# V2.net
KiCad netlist of a schematic drawn in EAGLE
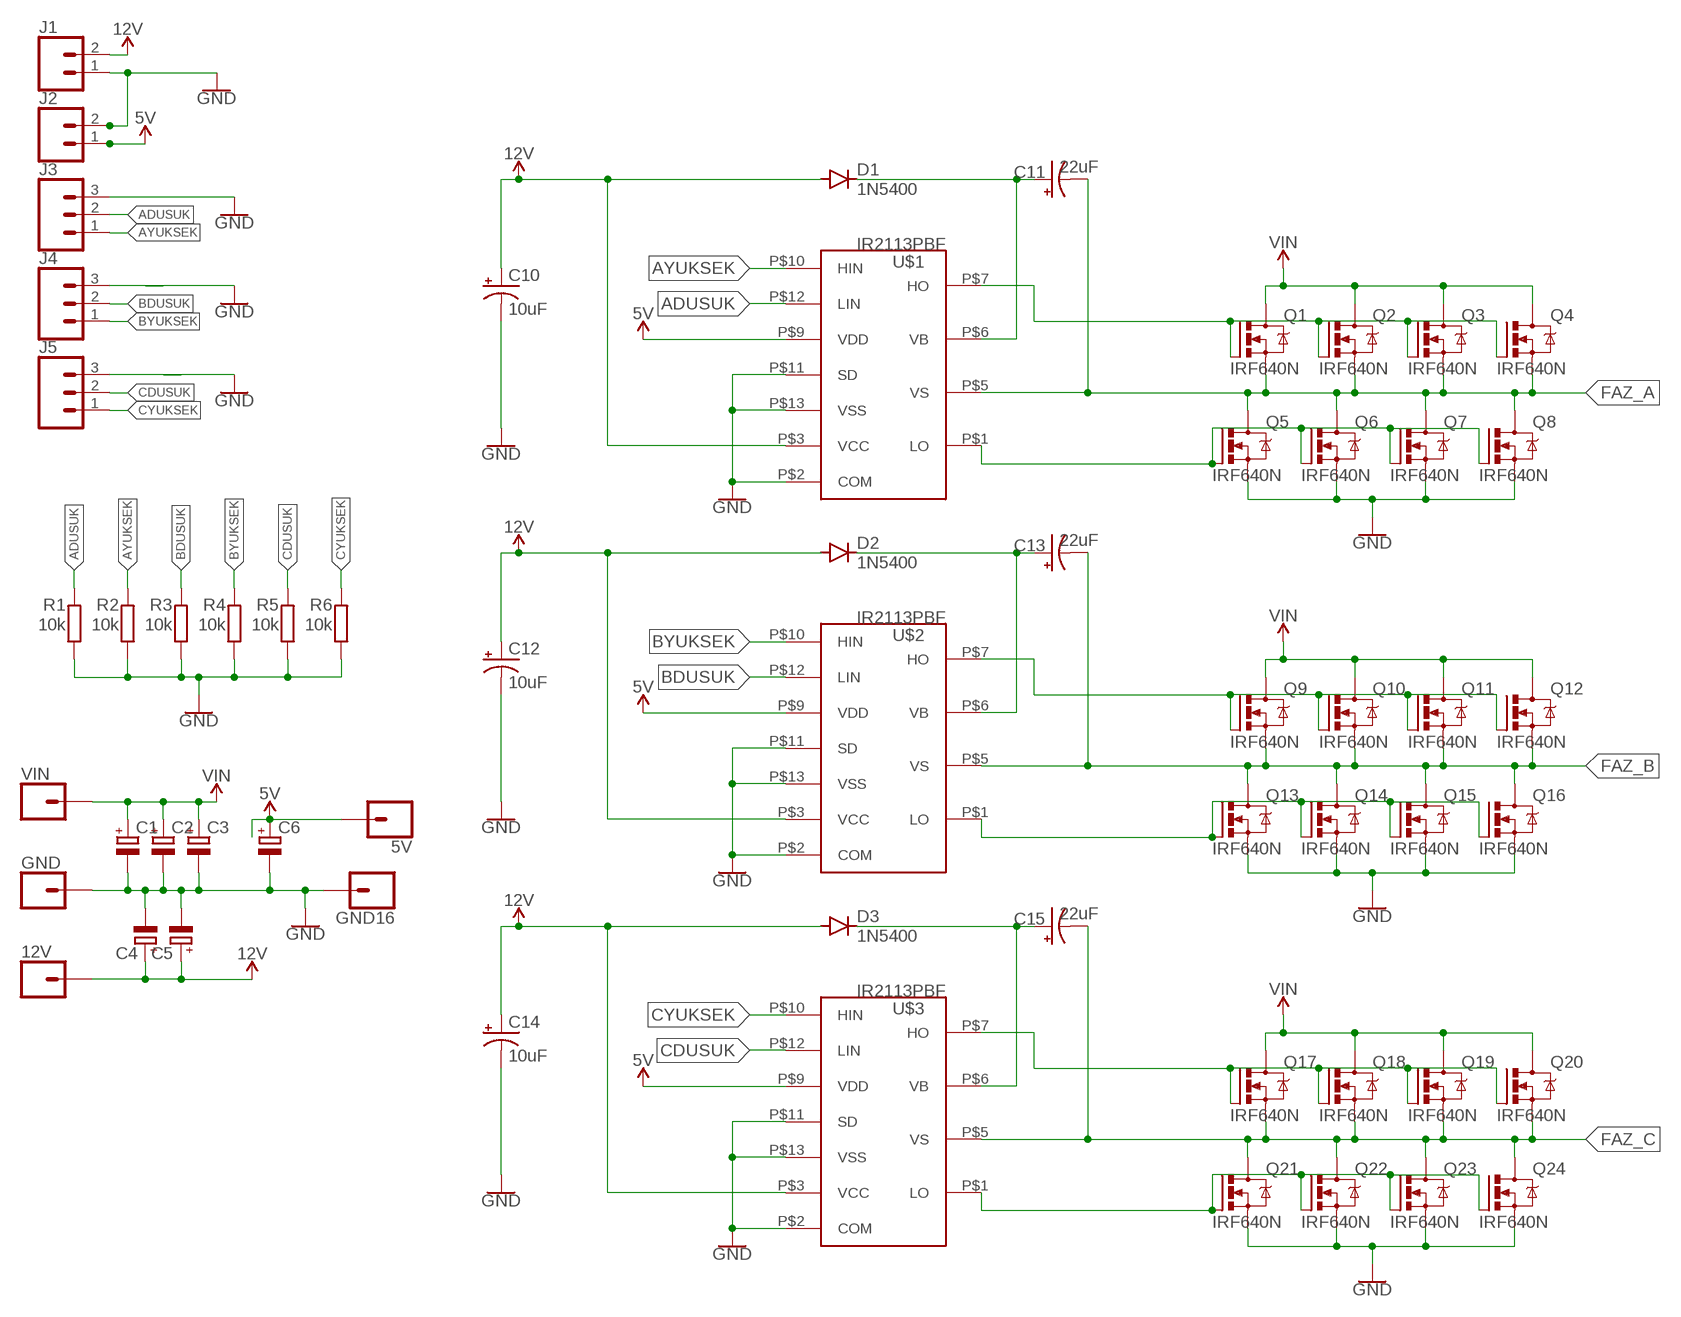
[diagram p0: schematic, sheet 1]

(export (version "E")
  (design (tool "Eeschema 10.0.6"))
  (components
    (comp (ref "5V")
      (value "CONN_01SNAP-MALE")
      (footprint "eagle-import:SNAP-MALE")
      (libsource (lib "eagle-import") (part "CONN_01SNAP-MALE"))
    )
    (comp (ref "12V")
      (value "CONN_01SNAP-MALE")
      (footprint "eagle-import:SNAP-MALE")
      (libsource (lib "eagle-import") (part "CONN_01SNAP-MALE"))
    )
    (comp (ref "C1")
      (value "16MM-DIA-CAPASITOR")
      (footprint "eagle-import:16MM-DIA-CAPASITOR")
      (libsource (lib "eagle-import") (part "16MM-DIA-CAPASITOR"))
    )
    (comp (ref "C2")
      (value "16MM-DIA-CAPASITOR")
      (footprint "eagle-import:16MM-DIA-CAPASITOR")
      (libsource (lib "eagle-import") (part "16MM-DIA-CAPASITOR"))
    )
    (comp (ref "C3")
      (value "16MM-DIA-CAPASITOR")
      (footprint "eagle-import:16MM-DIA-CAPASITOR")
      (libsource (lib "eagle-import") (part "16MM-DIA-CAPASITOR"))
    )
    (comp (ref "C4")
      (value "16MM-DIA-CAPASITOR")
      (footprint "eagle-import:16MM-DIA-CAPASITOR")
      (libsource (lib "eagle-import") (part "16MM-DIA-CAPASITOR"))
    )
    (comp (ref "C5")
      (value "16MM-DIA-CAPASITOR")
      (footprint "eagle-import:16MM-DIA-CAPASITOR")
      (libsource (lib "eagle-import") (part "16MM-DIA-CAPASITOR"))
    )
    (comp (ref "C6")
      (value "C-POL_RADIAL-25MM-DIA")
      (footprint "eagle-import:CAPPRD550W110D1250H2500B")
      (libsource (lib "eagle-import") (part "C-POLRADIAL-25MM-DIA_"))
    )
    (comp (ref "C10")
      (value "10uF")
      (footprint "eagle-import:CPOL-RADIAL-2.5MM-5MM")
      (libsource (lib "eagle-import") (part "10UF-POLAR-RADIAL-2.5MM-25V-20%"))
    )
    (comp (ref "C11")
      (value "22uF")
      (footprint "eagle-import:CPOL-RADIAL-2.5MM-5MM")
      (libsource (lib "eagle-import") (part "10UF-POLAR-RADIAL-2.5MM-25V-20%"))
    )
    (comp (ref "C12")
      (value "10uF")
      (footprint "eagle-import:CPOL-RADIAL-2.5MM-5MM")
      (libsource (lib "eagle-import") (part "10UF-POLAR-RADIAL-2.5MM-25V-20%"))
    )
    (comp (ref "C13")
      (value "22uF")
      (footprint "eagle-import:CPOL-RADIAL-2.5MM-5MM")
      (libsource (lib "eagle-import") (part "10UF-POLAR-RADIAL-2.5MM-25V-20%"))
    )
    (comp (ref "C14")
      (value "10uF")
      (footprint "eagle-import:CPOL-RADIAL-2.5MM-5MM")
      (libsource (lib "eagle-import") (part "10UF-POLAR-RADIAL-2.5MM-25V-20%"))
    )
    (comp (ref "C15")
      (value "22uF")
      (footprint "eagle-import:CPOL-RADIAL-2.5MM-5MM")
      (libsource (lib "eagle-import") (part "10UF-POLAR-RADIAL-2.5MM-25V-20%"))
    )
    (comp (ref "D1")
      (value "1N5400")
      (footprint "eagle-import:DO201-15")
      (libsource (lib "eagle-import") (part "1N5400"))
    )
    (comp (ref "D2")
      (value "1N5400")
      (footprint "eagle-import:DO201-15")
      (libsource (lib "eagle-import") (part "1N5400"))
    )
    (comp (ref "D3")
      (value "1N5400")
      (footprint "eagle-import:DO201-15")
      (libsource (lib "eagle-import") (part "1N5400"))
    )
    (comp (ref "GND")
      (value "CONN_01SNAP-MALE")
      (footprint "eagle-import:SNAP-MALE")
      (libsource (lib "eagle-import") (part "CONN_01SNAP-MALE"))
    )
    (comp (ref "GND16")
      (value "CONN_01SNAP-MALE")
      (footprint "eagle-import:SNAP-MALE")
      (libsource (lib "eagle-import") (part "CONN_01SNAP-MALE"))
    )
    (comp (ref "J1")
      (value "CONN_025MM")
      (footprint "eagle-import:SCREWTERMINAL-5MM-2")
      (libsource (lib "eagle-import") (part "CONN_025MM"))
    )
    (comp (ref "J2")
      (value "CONN_025MM")
      (footprint "eagle-import:SCREWTERMINAL-5MM-2")
      (libsource (lib "eagle-import") (part "CONN_025MM"))
    )
    (comp (ref "J3")
      (value "CONN_03-SCREW-5MM")
      (footprint "eagle-import:SCREWTERMINAL-5MM-3")
      (libsource (lib "eagle-import") (part "CONN_03-SCREW-5MM"))
    )
    (comp (ref "J4")
      (value "CONN_03-SCREW-5MM")
      (footprint "eagle-import:SCREWTERMINAL-5MM-3")
      (libsource (lib "eagle-import") (part "CONN_03-SCREW-5MM"))
    )
    (comp (ref "J5")
      (value "CONN_03-SCREW-5MM")
      (footprint "eagle-import:SCREWTERMINAL-5MM-3")
      (libsource (lib "eagle-import") (part "CONN_03-SCREW-5MM"))
    )
    (comp (ref "Q1")
      (value "IRF640N")
      (footprint "eagle-import:TO-220-PAD")
      (libsource (lib "eagle-import") (part "IRF640N"))
    )
    (comp (ref "Q2")
      (value "IRF640N")
      (footprint "eagle-import:TO-220-PAD")
      (libsource (lib "eagle-import") (part "IRF640N"))
    )
    (comp (ref "Q3")
      (value "IRF640N")
      (footprint "eagle-import:TO-220-PAD")
      (libsource (lib "eagle-import") (part "IRF640N"))
    )
    (comp (ref "Q4")
      (value "IRF640N")
      (footprint "eagle-import:TO-220-PAD")
      (libsource (lib "eagle-import") (part "IRF640N"))
    )
    (comp (ref "Q5")
      (value "IRF640N")
      (footprint "eagle-import:TO-220-PAD")
      (libsource (lib "eagle-import") (part "IRF640N"))
    )
    (comp (ref "Q6")
      (value "IRF640N")
      (footprint "eagle-import:TO-220-PAD")
      (libsource (lib "eagle-import") (part "IRF640N"))
    )
    (comp (ref "Q7")
      (value "IRF640N")
      (footprint "eagle-import:TO-220-PAD")
      (libsource (lib "eagle-import") (part "IRF640N"))
    )
    (comp (ref "Q8")
      (value "IRF640N")
      (footprint "eagle-import:TO-220-PAD")
      (libsource (lib "eagle-import") (part "IRF640N"))
    )
    (comp (ref "Q9")
      (value "IRF640N")
      (footprint "eagle-import:TO-220-PAD")
      (libsource (lib "eagle-import") (part "IRF640N"))
    )
    (comp (ref "Q10")
      (value "IRF640N")
      (footprint "eagle-import:TO-220-PAD")
      (libsource (lib "eagle-import") (part "IRF640N"))
    )
    (comp (ref "Q11")
      (value "IRF640N")
      (footprint "eagle-import:TO-220-PAD")
      (libsource (lib "eagle-import") (part "IRF640N"))
    )
    (comp (ref "Q12")
      (value "IRF640N")
      (footprint "eagle-import:TO-220-PAD")
      (libsource (lib "eagle-import") (part "IRF640N"))
    )
    (comp (ref "Q13")
      (value "IRF640N")
      (footprint "eagle-import:TO-220-PAD")
      (libsource (lib "eagle-import") (part "IRF640N"))
    )
    (comp (ref "Q14")
      (value "IRF640N")
      (footprint "eagle-import:TO-220-PAD")
      (libsource (lib "eagle-import") (part "IRF640N"))
    )
    (comp (ref "Q15")
      (value "IRF640N")
      (footprint "eagle-import:TO-220-PAD")
      (libsource (lib "eagle-import") (part "IRF640N"))
    )
    (comp (ref "Q16")
      (value "IRF640N")
      (footprint "eagle-import:TO-220-PAD")
      (libsource (lib "eagle-import") (part "IRF640N"))
    )
    (comp (ref "Q17")
      (value "IRF640N")
      (footprint "eagle-import:TO-220-PAD")
      (libsource (lib "eagle-import") (part "IRF640N"))
    )
    (comp (ref "Q18")
      (value "IRF640N")
      (footprint "eagle-import:TO-220-PAD")
      (libsource (lib "eagle-import") (part "IRF640N"))
    )
    (comp (ref "Q19")
      (value "IRF640N")
      (footprint "eagle-import:TO-220-PAD")
      (libsource (lib "eagle-import") (part "IRF640N"))
    )
    (comp (ref "Q20")
      (value "IRF640N")
      (footprint "eagle-import:TO-220-PAD")
      (libsource (lib "eagle-import") (part "IRF640N"))
    )
    (comp (ref "Q21")
      (value "IRF640N")
      (footprint "eagle-import:TO-220-PAD")
      (libsource (lib "eagle-import") (part "IRF640N"))
    )
    (comp (ref "Q22")
      (value "IRF640N")
      (footprint "eagle-import:TO-220-PAD")
      (libsource (lib "eagle-import") (part "IRF640N"))
    )
    (comp (ref "Q23")
      (value "IRF640N")
      (footprint "eagle-import:TO-220-PAD")
      (libsource (lib "eagle-import") (part "IRF640N"))
    )
    (comp (ref "Q24")
      (value "IRF640N")
      (footprint "eagle-import:TO-220-PAD")
      (libsource (lib "eagle-import") (part "IRF640N"))
    )
    (comp (ref "R1")
      (value "10k")
      (footprint "eagle-import:0207_10")
      (libsource (lib "eagle-import") (part "R-EU_0207/10"))
    )
    (comp (ref "R2")
      (value "10k")
      (footprint "eagle-import:0207_10")
      (libsource (lib "eagle-import") (part "R-EU_0207/10"))
    )
    (comp (ref "R3")
      (value "10k")
      (footprint "eagle-import:0207_10")
      (libsource (lib "eagle-import") (part "R-EU_0207/10"))
    )
    (comp (ref "R4")
      (value "10k")
      (footprint "eagle-import:0207_10")
      (libsource (lib "eagle-import") (part "R-EU_0207/10"))
    )
    (comp (ref "R5")
      (value "10k")
      (footprint "eagle-import:0207_10")
      (libsource (lib "eagle-import") (part "R-EU_0207/10"))
    )
    (comp (ref "R6")
      (value "10k")
      (footprint "eagle-import:0207_10")
      (libsource (lib "eagle-import") (part "R-EU_0207/10"))
    )
    (comp (ref "U$1")
      (value "IR2113PBF")
      (footprint "eagle-import:PDIP-14")
      (libsource (lib "eagle-import") (part "IR2113PBF"))
    )
    (comp (ref "U$2")
      (value "IR2113PBF")
      (footprint "eagle-import:PDIP-14")
      (libsource (lib "eagle-import") (part "IR2113PBF"))
    )
    (comp (ref "U$3")
      (value "IR2113PBF")
      (footprint "eagle-import:PDIP-14")
      (libsource (lib "eagle-import") (part "IR2113PBF"))
    )
    (comp (ref "VIN")
      (value "CONN_01SNAP-MALE")
      (footprint "eagle-import:SNAP-MALE")
      (libsource (lib "eagle-import") (part "CONN_01SNAP-MALE"))
    )
  )
  (nets
    (net (code "1") (name "5V") (class "Default")
      (node (ref "5V") (pin "2") (pinfunction "1_2") (pintype "passive"))
      (node (ref "C6") (pin "1") (pinfunction "+_1") (pintype "passive"))
      (node (ref "J2") (pin "1") (pinfunction "1_1") (pintype "passive"))
      (node (ref "U$1") (pin "P$9") (pinfunction "VDD_P$9") (pintype "bidirectional"))
      (node (ref "U$2") (pin "P$9") (pinfunction "VDD_P$9") (pintype "bidirectional"))
      (node (ref "U$3") (pin "P$9") (pinfunction "VDD_P$9") (pintype "bidirectional"))
    )
    (net (code "2") (name "12V") (class "Default")
      (node (ref "12V") (pin "2") (pinfunction "1_2") (pintype "passive"))
      (node (ref "C10") (pin "1") (pinfunction "+_1") (pintype "passive"))
      (node (ref "C12") (pin "1") (pinfunction "+_1") (pintype "passive"))
      (node (ref "C14") (pin "1") (pinfunction "+_1") (pintype "passive"))
      (node (ref "C4") (pin "+") (pinfunction "+_+") (pintype "passive"))
      (node (ref "C5") (pin "+") (pinfunction "+_+") (pintype "passive"))
      (node (ref "D1") (pin "A") (pinfunction "A_A") (pintype "passive"))
      (node (ref "D2") (pin "A") (pinfunction "A_A") (pintype "passive"))
      (node (ref "D3") (pin "A") (pinfunction "A_A") (pintype "passive"))
      (node (ref "J1") (pin "2") (pinfunction "2_2") (pintype "passive"))
      (node (ref "U$1") (pin "P$3") (pinfunction "VCC_P$3") (pintype "bidirectional"))
      (node (ref "U$2") (pin "P$3") (pinfunction "VCC_P$3") (pintype "bidirectional"))
      (node (ref "U$3") (pin "P$3") (pinfunction "VCC_P$3") (pintype "bidirectional"))
    )
    (net (code "3") (name "ADUSUK") (class "Default")
      (node (ref "J3") (pin "2") (pinfunction "2_2") (pintype "passive"))
      (node (ref "R1") (pin "2") (pinfunction "2_2") (pintype "passive"))
      (node (ref "U$1") (pin "P$12") (pinfunction "LIN_P$12") (pintype "bidirectional"))
    )
    (net (code "4") (name "AYUKSEK") (class "Default")
      (node (ref "J3") (pin "1") (pinfunction "1_1") (pintype "passive"))
      (node (ref "R2") (pin "2") (pinfunction "2_2") (pintype "passive"))
      (node (ref "U$1") (pin "P$10") (pinfunction "HIN_P$10") (pintype "bidirectional"))
    )
    (net (code "5") (name "BDUSUK") (class "Default")
      (node (ref "J4") (pin "2") (pinfunction "2_2") (pintype "passive"))
      (node (ref "R3") (pin "2") (pinfunction "2_2") (pintype "passive"))
      (node (ref "U$2") (pin "P$12") (pinfunction "LIN_P$12") (pintype "bidirectional"))
    )
    (net (code "6") (name "BYUKSEK") (class "Default")
      (node (ref "J4") (pin "1") (pinfunction "1_1") (pintype "passive"))
      (node (ref "R4") (pin "2") (pinfunction "2_2") (pintype "passive"))
      (node (ref "U$2") (pin "P$10") (pinfunction "HIN_P$10") (pintype "bidirectional"))
    )
    (net (code "7") (name "CDUSUK") (class "Default")
      (node (ref "J5") (pin "2") (pinfunction "2_2") (pintype "passive"))
      (node (ref "R5") (pin "2") (pinfunction "2_2") (pintype "passive"))
      (node (ref "U$3") (pin "P$12") (pinfunction "LIN_P$12") (pintype "bidirectional"))
    )
    (net (code "8") (name "CYUKSEK") (class "Default")
      (node (ref "J5") (pin "1") (pinfunction "1_1") (pintype "passive"))
      (node (ref "R6") (pin "2") (pinfunction "2_2") (pintype "passive"))
      (node (ref "U$3") (pin "P$10") (pinfunction "HIN_P$10") (pintype "bidirectional"))
    )
    (net (code "9") (name "FAZ_A") (class "Default")
      (node (ref "C11") (pin "2") (pinfunction "-_2") (pintype "passive"))
      (node (ref "Q1") (pin "3") (pinfunction "S_3") (pintype "passive"))
      (node (ref "Q2") (pin "3") (pinfunction "S_3") (pintype "passive"))
      (node (ref "Q3") (pin "3") (pinfunction "S_3") (pintype "passive"))
      (node (ref "Q4") (pin "3") (pinfunction "S_3") (pintype "passive"))
      (node (ref "Q5") (pin "TAB") (pinfunction "D_TAB") (pintype "passive"))
      (node (ref "Q6") (pin "TAB") (pinfunction "D_TAB") (pintype "passive"))
      (node (ref "Q7") (pin "TAB") (pinfunction "D_TAB") (pintype "passive"))
      (node (ref "Q8") (pin "TAB") (pinfunction "D_TAB") (pintype "passive"))
      (node (ref "U$1") (pin "P$5") (pinfunction "VS_P$5") (pintype "bidirectional"))
    )
    (net (code "10") (name "FAZ_B") (class "Default")
      (node (ref "C13") (pin "2") (pinfunction "-_2") (pintype "passive"))
      (node (ref "Q10") (pin "3") (pinfunction "S_3") (pintype "passive"))
      (node (ref "Q11") (pin "3") (pinfunction "S_3") (pintype "passive"))
      (node (ref "Q12") (pin "3") (pinfunction "S_3") (pintype "passive"))
      (node (ref "Q13") (pin "TAB") (pinfunction "D_TAB") (pintype "passive"))
      (node (ref "Q14") (pin "TAB") (pinfunction "D_TAB") (pintype "passive"))
      (node (ref "Q15") (pin "TAB") (pinfunction "D_TAB") (pintype "passive"))
      (node (ref "Q16") (pin "TAB") (pinfunction "D_TAB") (pintype "passive"))
      (node (ref "Q9") (pin "3") (pinfunction "S_3") (pintype "passive"))
      (node (ref "U$2") (pin "P$5") (pinfunction "VS_P$5") (pintype "bidirectional"))
    )
    (net (code "11") (name "FAZ_C") (class "Default")
      (node (ref "C15") (pin "2") (pinfunction "-_2") (pintype "passive"))
      (node (ref "Q17") (pin "3") (pinfunction "S_3") (pintype "passive"))
      (node (ref "Q18") (pin "3") (pinfunction "S_3") (pintype "passive"))
      (node (ref "Q19") (pin "3") (pinfunction "S_3") (pintype "passive"))
      (node (ref "Q20") (pin "3") (pinfunction "S_3") (pintype "passive"))
      (node (ref "Q21") (pin "TAB") (pinfunction "D_TAB") (pintype "passive"))
      (node (ref "Q22") (pin "TAB") (pinfunction "D_TAB") (pintype "passive"))
      (node (ref "Q23") (pin "TAB") (pinfunction "D_TAB") (pintype "passive"))
      (node (ref "Q24") (pin "TAB") (pinfunction "D_TAB") (pintype "passive"))
      (node (ref "U$3") (pin "P$5") (pinfunction "VS_P$5") (pintype "bidirectional"))
    )
    (net (code "12") (name "GND") (class "Default")
      (node (ref "C1") (pin "-") (pinfunction "-_-") (pintype "passive"))
      (node (ref "C10") (pin "2") (pinfunction "-_2") (pintype "passive"))
      (node (ref "C12") (pin "2") (pinfunction "-_2") (pintype "passive"))
      (node (ref "C14") (pin "2") (pinfunction "-_2") (pintype "passive"))
      (node (ref "C2") (pin "-") (pinfunction "-_-") (pintype "passive"))
      (node (ref "C3") (pin "-") (pinfunction "-_-") (pintype "passive"))
      (node (ref "C4") (pin "-") (pinfunction "-_-") (pintype "passive"))
      (node (ref "C5") (pin "-") (pinfunction "-_-") (pintype "passive"))
      (node (ref "C6") (pin "2") (pinfunction "-_2") (pintype "passive"))
      (node (ref "GND") (pin "2") (pinfunction "1_2") (pintype "passive"))
      (node (ref "GND16") (pin "2") (pinfunction "1_2") (pintype "passive"))
      (node (ref "J1") (pin "1") (pinfunction "1_1") (pintype "passive"))
      (node (ref "J2") (pin "2") (pinfunction "2_2") (pintype "passive"))
      (node (ref "J3") (pin "3") (pinfunction "3_3") (pintype "passive"))
      (node (ref "J4") (pin "3") (pinfunction "3_3") (pintype "passive"))
      (node (ref "J5") (pin "3") (pinfunction "3_3") (pintype "passive"))
      (node (ref "Q13") (pin "3") (pinfunction "S_3") (pintype "passive"))
      (node (ref "Q14") (pin "3") (pinfunction "S_3") (pintype "passive"))
      (node (ref "Q15") (pin "3") (pinfunction "S_3") (pintype "passive"))
      (node (ref "Q16") (pin "3") (pinfunction "S_3") (pintype "passive"))
      (node (ref "Q21") (pin "3") (pinfunction "S_3") (pintype "passive"))
      (node (ref "Q22") (pin "3") (pinfunction "S_3") (pintype "passive"))
      (node (ref "Q23") (pin "3") (pinfunction "S_3") (pintype "passive"))
      (node (ref "Q24") (pin "3") (pinfunction "S_3") (pintype "passive"))
      (node (ref "Q5") (pin "3") (pinfunction "S_3") (pintype "passive"))
      (node (ref "Q6") (pin "3") (pinfunction "S_3") (pintype "passive"))
      (node (ref "Q7") (pin "3") (pinfunction "S_3") (pintype "passive"))
      (node (ref "Q8") (pin "3") (pinfunction "S_3") (pintype "passive"))
      (node (ref "R1") (pin "1") (pinfunction "1_1") (pintype "passive"))
      (node (ref "R2") (pin "1") (pinfunction "1_1") (pintype "passive"))
      (node (ref "R3") (pin "1") (pinfunction "1_1") (pintype "passive"))
      (node (ref "R4") (pin "1") (pinfunction "1_1") (pintype "passive"))
      (node (ref "R5") (pin "1") (pinfunction "1_1") (pintype "passive"))
      (node (ref "R6") (pin "1") (pinfunction "1_1") (pintype "passive"))
      (node (ref "U$1") (pin "P$11") (pinfunction "SD_P$11") (pintype "bidirectional"))
      (node (ref "U$1") (pin "P$13") (pinfunction "VSS_P$13") (pintype "bidirectional"))
      (node (ref "U$1") (pin "P$2") (pinfunction "COM_P$2") (pintype "bidirectional"))
      (node (ref "U$2") (pin "P$11") (pinfunction "SD_P$11") (pintype "bidirectional"))
      (node (ref "U$2") (pin "P$13") (pinfunction "VSS_P$13") (pintype "bidirectional"))
      (node (ref "U$2") (pin "P$2") (pinfunction "COM_P$2") (pintype "bidirectional"))
      (node (ref "U$3") (pin "P$11") (pinfunction "SD_P$11") (pintype "bidirectional"))
      (node (ref "U$3") (pin "P$13") (pinfunction "VSS_P$13") (pintype "bidirectional"))
      (node (ref "U$3") (pin "P$2") (pinfunction "COM_P$2") (pintype "bidirectional"))
    )
    (net (code "13") (name "Net-(C11-+)") (class "Default")
      (node (ref "C11") (pin "1") (pinfunction "+_1") (pintype "passive"))
      (node (ref "D1") (pin "C") (pinfunction "C_C") (pintype "passive"))
      (node (ref "U$1") (pin "P$6") (pinfunction "VB_P$6") (pintype "bidirectional"))
    )
    (net (code "14") (name "Net-(C13-+)") (class "Default")
      (node (ref "C13") (pin "1") (pinfunction "+_1") (pintype "passive"))
      (node (ref "D2") (pin "C") (pinfunction "C_C") (pintype "passive"))
      (node (ref "U$2") (pin "P$6") (pinfunction "VB_P$6") (pintype "bidirectional"))
    )
    (net (code "15") (name "Net-(C15-+)") (class "Default")
      (node (ref "C15") (pin "1") (pinfunction "+_1") (pintype "passive"))
      (node (ref "D3") (pin "C") (pinfunction "C_C") (pintype "passive"))
      (node (ref "U$3") (pin "P$6") (pinfunction "VB_P$6") (pintype "bidirectional"))
    )
    (net (code "16") (name "Net-(Q1-G)") (class "Default")
      (node (ref "Q1") (pin "1") (pinfunction "G_1") (pintype "passive"))
      (node (ref "Q2") (pin "1") (pinfunction "G_1") (pintype "passive"))
      (node (ref "Q3") (pin "1") (pinfunction "G_1") (pintype "passive"))
      (node (ref "Q4") (pin "1") (pinfunction "G_1") (pintype "passive"))
      (node (ref "U$1") (pin "P$7") (pinfunction "HO_P$7") (pintype "bidirectional"))
    )
    (net (code "17") (name "Net-(Q5-G)") (class "Default")
      (node (ref "Q5") (pin "1") (pinfunction "G_1") (pintype "passive"))
      (node (ref "Q6") (pin "1") (pinfunction "G_1") (pintype "passive"))
      (node (ref "Q7") (pin "1") (pinfunction "G_1") (pintype "passive"))
      (node (ref "Q8") (pin "1") (pinfunction "G_1") (pintype "passive"))
      (node (ref "U$1") (pin "P$1") (pinfunction "LO_P$1") (pintype "bidirectional"))
    )
    (net (code "18") (name "Net-(Q10-G)") (class "Default")
      (node (ref "Q10") (pin "1") (pinfunction "G_1") (pintype "passive"))
      (node (ref "Q11") (pin "1") (pinfunction "G_1") (pintype "passive"))
      (node (ref "Q12") (pin "1") (pinfunction "G_1") (pintype "passive"))
      (node (ref "Q9") (pin "1") (pinfunction "G_1") (pintype "passive"))
      (node (ref "U$2") (pin "P$7") (pinfunction "HO_P$7") (pintype "bidirectional"))
    )
    (net (code "19") (name "Net-(Q13-G)") (class "Default")
      (node (ref "Q13") (pin "1") (pinfunction "G_1") (pintype "passive"))
      (node (ref "Q14") (pin "1") (pinfunction "G_1") (pintype "passive"))
      (node (ref "Q15") (pin "1") (pinfunction "G_1") (pintype "passive"))
      (node (ref "Q16") (pin "1") (pinfunction "G_1") (pintype "passive"))
      (node (ref "U$2") (pin "P$1") (pinfunction "LO_P$1") (pintype "bidirectional"))
    )
    (net (code "20") (name "Net-(Q17-G)") (class "Default")
      (node (ref "Q17") (pin "1") (pinfunction "G_1") (pintype "passive"))
      (node (ref "Q18") (pin "1") (pinfunction "G_1") (pintype "passive"))
      (node (ref "Q19") (pin "1") (pinfunction "G_1") (pintype "passive"))
      (node (ref "Q20") (pin "1") (pinfunction "G_1") (pintype "passive"))
      (node (ref "U$3") (pin "P$7") (pinfunction "HO_P$7") (pintype "bidirectional"))
    )
    (net (code "21") (name "Net-(Q21-G)") (class "Default")
      (node (ref "Q21") (pin "1") (pinfunction "G_1") (pintype "passive"))
      (node (ref "Q22") (pin "1") (pinfunction "G_1") (pintype "passive"))
      (node (ref "Q23") (pin "1") (pinfunction "G_1") (pintype "passive"))
      (node (ref "Q24") (pin "1") (pinfunction "G_1") (pintype "passive"))
      (node (ref "U$3") (pin "P$1") (pinfunction "LO_P$1") (pintype "bidirectional"))
    )
    (net (code "22") (name "VIN") (class "Default")
      (node (ref "C1") (pin "+") (pinfunction "+_+") (pintype "passive"))
      (node (ref "C2") (pin "+") (pinfunction "+_+") (pintype "passive"))
      (node (ref "C3") (pin "+") (pinfunction "+_+") (pintype "passive"))
      (node (ref "Q1") (pin "TAB") (pinfunction "D_TAB") (pintype "passive"))
      (node (ref "Q10") (pin "TAB") (pinfunction "D_TAB") (pintype "passive"))
      (node (ref "Q11") (pin "TAB") (pinfunction "D_TAB") (pintype "passive"))
      (node (ref "Q12") (pin "TAB") (pinfunction "D_TAB") (pintype "passive"))
      (node (ref "Q17") (pin "TAB") (pinfunction "D_TAB") (pintype "passive"))
      (node (ref "Q18") (pin "TAB") (pinfunction "D_TAB") (pintype "passive"))
      (node (ref "Q19") (pin "TAB") (pinfunction "D_TAB") (pintype "passive"))
      (node (ref "Q2") (pin "TAB") (pinfunction "D_TAB") (pintype "passive"))
      (node (ref "Q20") (pin "TAB") (pinfunction "D_TAB") (pintype "passive"))
      (node (ref "Q3") (pin "TAB") (pinfunction "D_TAB") (pintype "passive"))
      (node (ref "Q4") (pin "TAB") (pinfunction "D_TAB") (pintype "passive"))
      (node (ref "Q9") (pin "TAB") (pinfunction "D_TAB") (pintype "passive"))
      (node (ref "VIN") (pin "2") (pinfunction "1_2") (pintype "passive"))
    )
  )
)
